# Motor_Board.net
KiCad netlist of a schematic drawn in Altium Designer
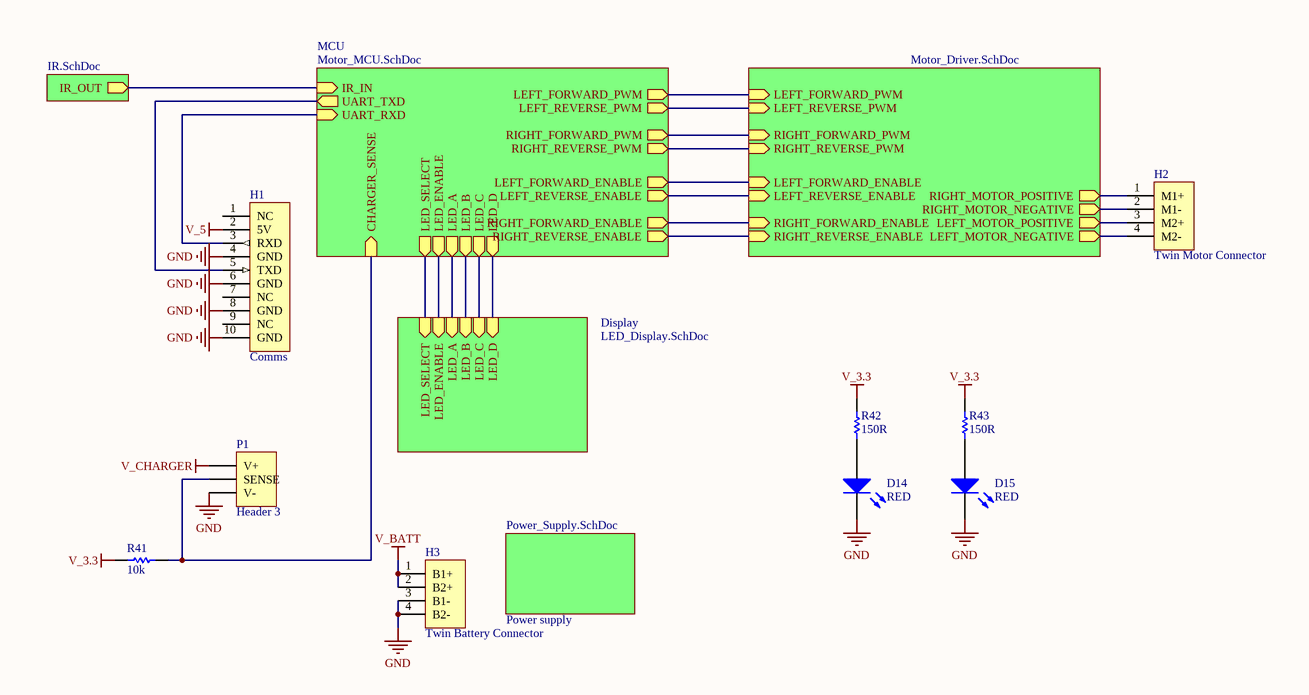
[diagram p0: Motor_Board.SchDoc]

(export (version "E")
  (design (tool "Eeschema 10.0.6"))
  (components
    (comp (ref "D14")
      (value "RED")
      (footprint "Diode_0805")
      (description "Red LED 0805")
      (fields (field (name "MANUFACTURER") "Vishay") (field (name "PART NUMBER") "DL_LED Red 0805"))
      (libsource (lib "ENEL429_4") (part "DL_LED Red 0805"))
    )
    (comp (ref "D15")
      (value "RED")
      (footprint "Diode_0805")
      (description "Red LED 0805")
      (fields (field (name "MANUFACTURER") "Vishay") (field (name "PART NUMBER") "DL_LED Red 0805"))
      (libsource (lib "ENEL429_4") (part "DL_LED Red 0805"))
    )
    (comp (ref "H1")
      (value "Comms")
      (footprint "918510x323")
      (description "Header, IDC 10-Pin")
      (fields (field (name "PUBLISHER") "Altium Limited"))
      (libsource (lib "Wacky_1") (part "Header 10"))
    )
    (comp (ref "H2")
      (value "Twin Motor Connector")
      (footprint "TMHDR4")
      (description "5.08mm Pluggable Terminal Header")
      (fields (field (name "PUBLISHER") "Altium Limited"))
      (libsource (lib "Wacky_1") (part "AVR ISP Header 4"))
    )
    (comp (ref "H3")
      (value "Twin Battery Connector")
      (footprint "TMHDR4")
      (description "5.08mm Pluggable Terminal Header")
      (fields (field (name "PUBLISHER") "Altium Limited"))
      (libsource (lib "Wacky_1") (part "AVR ISP Header 4"))
    )
    (comp (ref "P1")
      (value "Header 3")
      (footprint "DC power jack")
      (description "Header, 3-Pin")
      (fields (field (name "PUBLISHER") "Altium Limited"))
      (libsource (lib "Miscellaneous Connectors") (part "Header 3"))
    )
    (comp (ref "R41")
      (value "10k")
      (footprint "0603")
      (description "RES 10.0K OHM 1/10W 1% 0603 SMD")
      (fields (field (name "MANUFACTURER") "Yageo") (field (name "PART NUMBER") "RS_10k 0603"))
      (libsource (lib "ENEL429_4") (part "RS_10k 0603"))
    )
    (comp (ref "R42")
      (value "150R")
      (footprint "0603")
      (description "RES 150 OHM 1/10W 1% 0603 SMD")
      (fields (field (name "MANUFACTURER") "ROHM") (field (name "PART NUMBER") "RS_150R 0603"))
      (libsource (lib "ENEL429_4") (part "RS_150R 0603"))
    )
    (comp (ref "R43")
      (value "150R")
      (footprint "0603")
      (description "RES 150 OHM 1/10W 1% 0603 SMD")
      (fields (field (name "MANUFACTURER") "ROHM") (field (name "PART NUMBER") "RS_150R 0603"))
      (libsource (lib "ENEL429_4") (part "RS_150R 0603"))
    )
  )
  (nets
    (net (code "1") (name "/CHARGER_SENSE") (class "Default")
      (node (ref "P1") (pin "2") (pinfunction "SENSE_2") (pintype "passive"))
      (node (ref "R41") (pin "2") (pinfunction "2_2") (pintype "passive"))
    )
    (net (code "11") (name "/LEFT_MOTOR_NEGATIVE") (class "Default")
      (node (ref "H2") (pin "4") (pinfunction "B2-_4") (pintype "passive"))
    )
    (net (code "12") (name "/LEFT_MOTOR_POSITIVE") (class "Default")
      (node (ref "H2") (pin "3") (pinfunction "B1-_3") (pintype "passive"))
    )
    (net (code "17") (name "/RIGHT_MOTOR_NEGATIVE") (class "Default")
      (node (ref "H2") (pin "2") (pinfunction "B2+_2") (pintype "passive"))
    )
    (net (code "18") (name "/RIGHT_MOTOR_POSITIVE") (class "Default")
      (node (ref "H2") (pin "1") (pinfunction "B1+_1") (pintype "passive"))
    )
    (net (code "21") (name "/UART_RXD") (class "Default")
      (node (ref "H1") (pin "3") (pinfunction "RXD_3") (pintype "output"))
    )
    (net (code "22") (name "/UART_TXD") (class "Default")
      (node (ref "H1") (pin "5") (pinfunction "TXD_5") (pintype "input"))
    )
    (net (code "23") (name "GND") (class "Default")
      (node (ref "D14") (pin "2") (pinfunction "K_2") (pintype "passive"))
      (node (ref "D15") (pin "2") (pinfunction "K_2") (pintype "passive"))
      (node (ref "H1") (pin "10") (pinfunction "GND_10") (pintype "power_in"))
      (node (ref "H1") (pin "4") (pinfunction "GND_4") (pintype "power_in"))
      (node (ref "H1") (pin "6") (pinfunction "GND_6") (pintype "power_in"))
      (node (ref "H1") (pin "8") (pinfunction "GND_8") (pintype "power_in"))
      (node (ref "H3") (pin "3") (pinfunction "B1-_3") (pintype "passive"))
      (node (ref "H3") (pin "4") (pinfunction "B2-_4") (pintype "passive"))
      (node (ref "P1") (pin "3") (pinfunction "V-_3") (pintype "passive"))
    )
    (net (code "24") (name "Net-(D14-A)") (class "Default")
      (node (ref "D14") (pin "1") (pinfunction "A_1") (pintype "passive"))
      (node (ref "R42") (pin "1") (pinfunction "1_1") (pintype "passive"))
    )
    (net (code "25") (name "Net-(D15-A)") (class "Default")
      (node (ref "D15") (pin "1") (pinfunction "A_1") (pintype "passive"))
      (node (ref "R43") (pin "1") (pinfunction "1_1") (pintype "passive"))
    )
    (net (code "26") (name "V_3.3") (class "Default")
      (node (ref "R41") (pin "1") (pinfunction "1_1") (pintype "passive"))
      (node (ref "R42") (pin "2") (pinfunction "2_2") (pintype "passive"))
      (node (ref "R43") (pin "2") (pinfunction "2_2") (pintype "passive"))
    )
    (net (code "27") (name "V_5") (class "Default")
      (node (ref "H1") (pin "2") (pinfunction "5V_2") (pintype "power_in"))
    )
    (net (code "28") (name "V_BATT") (class "Default")
      (node (ref "H3") (pin "1") (pinfunction "B1+_1") (pintype "passive"))
      (node (ref "H3") (pin "2") (pinfunction "B2+_2") (pintype "passive"))
    )
    (net (code "29") (name "V_CHARGER") (class "Default")
      (node (ref "P1") (pin "1") (pinfunction "V+_1") (pintype "passive"))
    )
    (net (code "30") (name "unconnected-(H1-NC-Pad1)") (class "Default")
      (node (ref "H1") (pin "1") (pinfunction "NC_1") (pintype "passive"))
    )
    (net (code "31") (name "unconnected-(H1-NC-Pad7)") (class "Default")
      (node (ref "H1") (pin "7") (pinfunction "NC_7") (pintype "passive"))
    )
    (net (code "32") (name "unconnected-(H1-NC-Pad9)") (class "Default")
      (node (ref "H1") (pin "9") (pinfunction "NC_9") (pintype "passive"))
    )
  )
)
